# Sheet1.net
KiCad netlist of a schematic drawn in Altium Designer
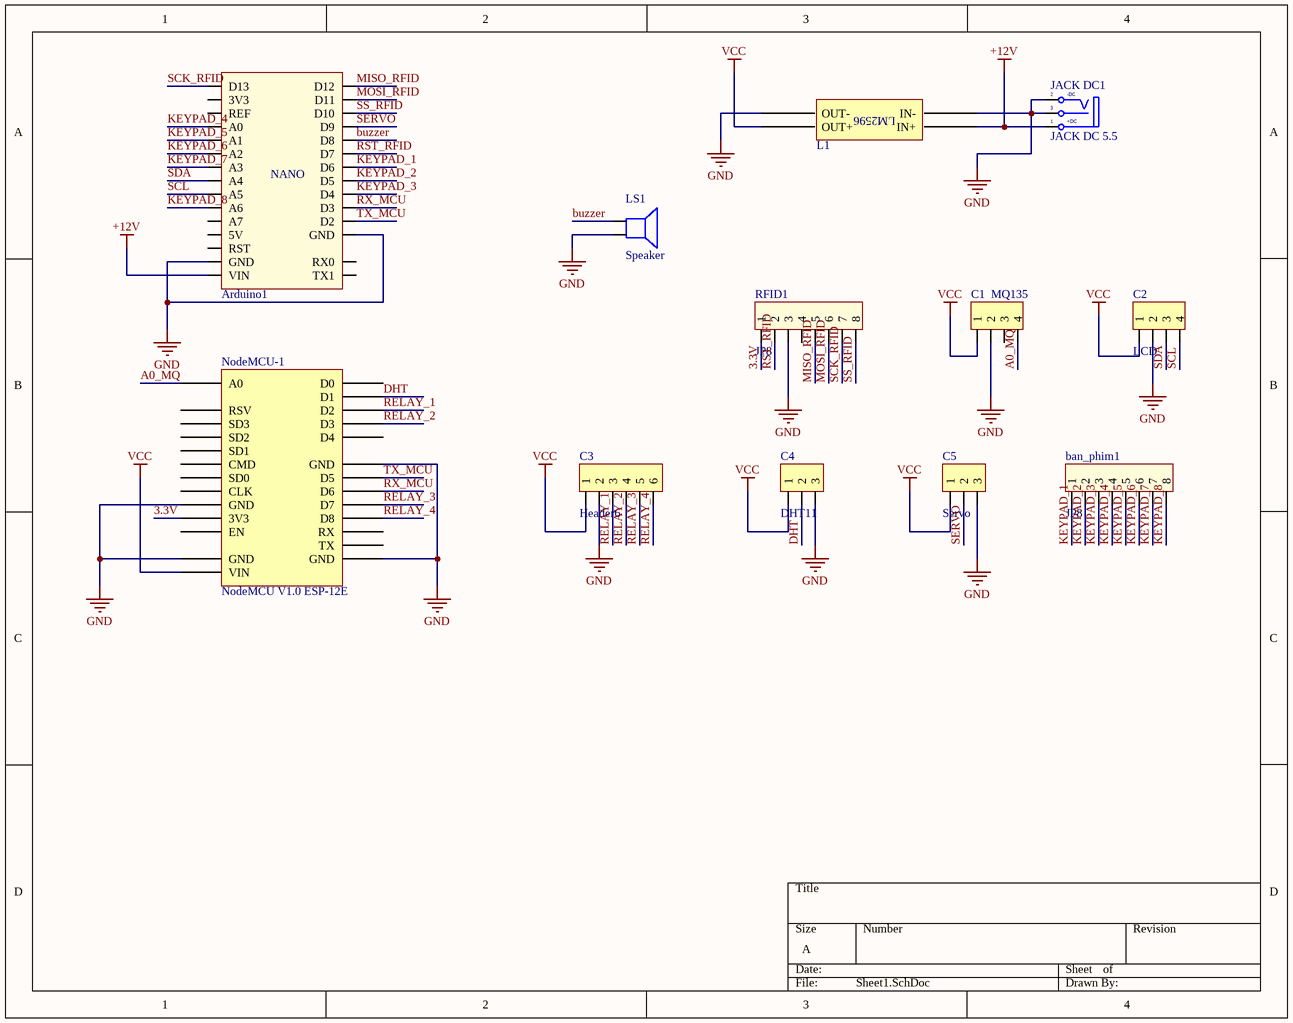
[diagram p0: Sheet1.SchDoc]

(export (version "E")
  (design (tool "Eeschema 10.0.6"))
  (components
    (comp (ref "Arduino1")
      (value "Arduino Nano")
      (footprint "Arduino Nano")
      (description "Arduino NANO")
      (libsource (lib "LIBRARY") (part "Arduino Nano"))
    )
    (comp (ref "ban_phim1")
      (value "JP8")
      (footprint "Header8")
      (description "Connector 8")
      (libsource (lib "LIBRARY") (part "Header8"))
    )
    (comp (ref "C1")
      (value "MQ135")
      (footprint "HDR4")
      (description "Header IDC, 4 x 1 Pin Vertical 2.54mm Pitch (Non-Boxed, Male)")
      (fields
        (field (name "MANUFACTURER") "Würth Elektronik eiSos GmbH")
        (field (name "PARTNO") "613002143121")
        (field (name "CREATED BY") "Karrer Zheng")
      )
      (libsource (lib "LIBRARY") (part "Header4"))
    )
    (comp (ref "C2")
      (value "LCD")
      (footprint "HDR4")
      (description "Header IDC, 4 x 1 Pin Vertical 2.54mm Pitch (Non-Boxed, Male)")
      (fields
        (field (name "MANUFACTURER") "Würth Elektronik eiSos GmbH")
        (field (name "PARTNO") "613002143121")
        (field (name "CREATED BY") "Karrer Zheng")
      )
      (libsource (lib "LIBRARY") (part "Header4"))
    )
    (comp (ref "C3")
      (value "Header6")
      (footprint "HDR6")
      (description "Header IDC, 6 x 1 Pin Vertical 2.54mm Pitch (Non-Boxed, Male)")
      (fields
        (field (name "MANUFACTURER") "Würth Elektronik eiSos GmbH")
        (field (name "PARTNO") "613002143121")
        (field (name "CREATED BY") "Karrer Zheng")
      )
      (libsource (lib "LIBRARY") (part "Header6"))
    )
    (comp (ref "C4")
      (value "DHT11")
      (footprint "HDR3")
      (description "Header IDC, 3 x 1 Pin Vertical 2.54mm Pitch (Non-Boxed, Male)")
      (fields
        (field (name "MANUFACTURER") "Würth Elektronik eiSos GmbH")
        (field (name "PARTNO") "613002143121")
        (field (name "CREATED BY") "Karrer Zheng")
      )
      (libsource (lib "LIBRARY") (part "Header3"))
    )
    (comp (ref "C5")
      (value "Servo")
      (footprint "HDR3")
      (description "Header IDC, 3 x 1 Pin Vertical 2.54mm Pitch (Non-Boxed, Male)")
      (fields
        (field (name "MANUFACTURER") "Würth Elektronik eiSos GmbH")
        (field (name "PARTNO") "613002143121")
        (field (name "CREATED BY") "Karrer Zheng")
      )
      (libsource (lib "LIBRARY") (part "Header3"))
    )
    (comp (ref "JACK DC1")
      (value "JACK DC 5.5")
      (footprint "JACK DC 5.5")
      (libsource (lib "LinhKienMCU.com") (part "JACK DC 5.5"))
    )
    (comp (ref "L1")
      (value "BUCK_LM2596")
      (footprint "BUCK_LM2596")
      (libsource (lib "BUCK_LM2596_Sch") (part "BUCK_LM2596"))
    )
    (comp (ref "LS1")
      (value "Speaker")
      (footprint "SPEAKER")
      (description "Loudspeaker")
      (fields (field (name "PUBLISHER") "Altium Limited"))
      (libsource (lib "LIBRARY") (part "Speaker"))
    )
    (comp (ref "NodeMCU-1")
      (value "NodeMCU V1.0 ESP-12E")
      (footprint "NodeMCU V1.0 ESP-12E")
      (description "NodeMCU V1.0 ESP8266 (ESP-12E)")
      (libsource (lib "nodemcu") (part "NodeMCU V1.0 ESP-12E"))
    )
    (comp (ref "RFID1")
      (value "JP8")
      (footprint "Header8")
      (description "Connector 8")
      (libsource (lib "LIBRARY") (part "Header8"))
    )
  )
  (nets
    (net (code "1") (name "+12V") (class "Default")
      (node (ref "Arduino1") (pin "VIN") (pinfunction "VIN_VIN") (pintype "passive"))
      (node (ref "JACK DC1") (pin "1") (pinfunction "T_1") (pintype "passive"))
      (node (ref "L1") (pin "1") (pinfunction "IN+_1") (pintype "passive"))
    )
    (net (code "2") (name "/3.3V") (class "Default")
      (node (ref "NodeMCU-1") (pin "3V3") (pinfunction "3V3_3V3") (pintype "passive"))
      (node (ref "RFID1") (pin "1") (pinfunction "1_1") (pintype "passive"))
    )
    (net (code "3") (name "/A0_MQ") (class "Default")
      (node (ref "C1") (pin "4") (pinfunction "4_4") (pintype "passive"))
      (node (ref "NodeMCU-1") (pin "A0") (pinfunction "A0_A0") (pintype "passive"))
    )
    (net (code "4") (name "/DHT") (class "Default")
      (node (ref "C4") (pin "2") (pinfunction "2_2") (pintype "passive"))
      (node (ref "NodeMCU-1") (pin "D1") (pinfunction "D1_D1") (pintype "passive"))
    )
    (net (code "5") (name "/KEYPAD_1") (class "Default")
      (node (ref "Arduino1") (pin "D6") (pinfunction "D6_D6") (pintype "passive"))
      (node (ref "ban_phim1") (pin "1") (pinfunction "1_1") (pintype "passive"))
    )
    (net (code "6") (name "/KEYPAD_2") (class "Default")
      (node (ref "Arduino1") (pin "D5") (pinfunction "D5_D5") (pintype "passive"))
      (node (ref "ban_phim1") (pin "2") (pinfunction "2_2") (pintype "passive"))
    )
    (net (code "7") (name "/KEYPAD_3") (class "Default")
      (node (ref "Arduino1") (pin "D4") (pinfunction "D4_D4") (pintype "passive"))
      (node (ref "ban_phim1") (pin "3") (pinfunction "3_3") (pintype "passive"))
    )
    (net (code "8") (name "/KEYPAD_4") (class "Default")
      (node (ref "Arduino1") (pin "A0") (pinfunction "A0_A0") (pintype "passive"))
      (node (ref "ban_phim1") (pin "4") (pinfunction "4_4") (pintype "passive"))
    )
    (net (code "9") (name "/KEYPAD_5") (class "Default")
      (node (ref "Arduino1") (pin "A1") (pinfunction "A1_A1") (pintype "passive"))
      (node (ref "ban_phim1") (pin "5") (pinfunction "5_5") (pintype "passive"))
    )
    (net (code "10") (name "/KEYPAD_6") (class "Default")
      (node (ref "Arduino1") (pin "A2") (pinfunction "A2_A2") (pintype "passive"))
      (node (ref "ban_phim1") (pin "6") (pinfunction "6_6") (pintype "passive"))
    )
    (net (code "11") (name "/KEYPAD_7") (class "Default")
      (node (ref "Arduino1") (pin "A3") (pinfunction "A3_A3") (pintype "passive"))
      (node (ref "ban_phim1") (pin "7") (pinfunction "7_7") (pintype "passive"))
    )
    (net (code "12") (name "/KEYPAD_8") (class "Default")
      (node (ref "Arduino1") (pin "A6") (pinfunction "A6_A6") (pintype "passive"))
      (node (ref "ban_phim1") (pin "8") (pinfunction "8_8") (pintype "passive"))
    )
    (net (code "13") (name "/MISO_RFID") (class "Default")
      (node (ref "Arduino1") (pin "D12") (pinfunction "D12_D12") (pintype "passive"))
      (node (ref "RFID1") (pin "5") (pinfunction "5_5") (pintype "passive"))
    )
    (net (code "14") (name "/MOSI_RFID") (class "Default")
      (node (ref "Arduino1") (pin "D11") (pinfunction "D11_D11") (pintype "passive"))
      (node (ref "RFID1") (pin "6") (pinfunction "6_6") (pintype "passive"))
    )
    (net (code "15") (name "/RELAY_1") (class "Default")
      (node (ref "C3") (pin "3") (pinfunction "3_3") (pintype "passive"))
      (node (ref "NodeMCU-1") (pin "D2") (pinfunction "D2_D2") (pintype "passive"))
    )
    (net (code "16") (name "/RELAY_2") (class "Default")
      (node (ref "C3") (pin "4") (pinfunction "4_4") (pintype "passive"))
      (node (ref "NodeMCU-1") (pin "D3") (pinfunction "D3_D3") (pintype "passive"))
    )
    (net (code "17") (name "/RELAY_3") (class "Default")
      (node (ref "C3") (pin "5") (pinfunction "5_5") (pintype "passive"))
      (node (ref "NodeMCU-1") (pin "D7") (pinfunction "D7_D7") (pintype "passive"))
    )
    (net (code "18") (name "/RELAY_4") (class "Default")
      (node (ref "C3") (pin "6") (pinfunction "6_6") (pintype "passive"))
      (node (ref "NodeMCU-1") (pin "D8") (pinfunction "D8_D8") (pintype "passive"))
    )
    (net (code "19") (name "/RST_RFID") (class "Default")
      (node (ref "Arduino1") (pin "D7") (pinfunction "D7_D7") (pintype "passive"))
      (node (ref "RFID1") (pin "2") (pinfunction "2_2") (pintype "passive"))
    )
    (net (code "20") (name "/RX_MCU") (class "Default")
      (node (ref "Arduino1") (pin "D3") (pinfunction "D3_D3") (pintype "passive"))
      (node (ref "NodeMCU-1") (pin "D6") (pinfunction "D6_D6") (pintype "passive"))
    )
    (net (code "21") (name "/SCK_RFID") (class "Default")
      (node (ref "Arduino1") (pin "D13") (pinfunction "D13_D13") (pintype "passive"))
      (node (ref "RFID1") (pin "7") (pinfunction "7_7") (pintype "passive"))
    )
    (net (code "22") (name "/SCL") (class "Default")
      (node (ref "Arduino1") (pin "A5") (pinfunction "A5_A5") (pintype "passive"))
      (node (ref "C2") (pin "4") (pinfunction "4_4") (pintype "passive"))
    )
    (net (code "23") (name "/SDA") (class "Default")
      (node (ref "Arduino1") (pin "A4") (pinfunction "A4_A4") (pintype "passive"))
      (node (ref "C2") (pin "3") (pinfunction "3_3") (pintype "passive"))
    )
    (net (code "24") (name "/SERVO") (class "Default")
      (node (ref "Arduino1") (pin "D9") (pinfunction "D9_D9") (pintype "passive"))
      (node (ref "C5") (pin "2") (pinfunction "2_2") (pintype "passive"))
    )
    (net (code "25") (name "/SS_RFID") (class "Default")
      (node (ref "Arduino1") (pin "D10") (pinfunction "D10_D10") (pintype "passive"))
      (node (ref "RFID1") (pin "8") (pinfunction "8_8") (pintype "passive"))
    )
    (net (code "26") (name "/TX_MCU") (class "Default")
      (node (ref "Arduino1") (pin "D2") (pinfunction "D2_D2") (pintype "passive"))
      (node (ref "NodeMCU-1") (pin "D5") (pinfunction "D5_D5") (pintype "passive"))
    )
    (net (code "27") (name "/buzzer") (class "Default")
      (node (ref "Arduino1") (pin "D8") (pinfunction "D8_D8") (pintype "passive"))
      (node (ref "LS1") (pin "1") (pinfunction "1_1") (pintype "passive"))
    )
    (net (code "28") (name "GND") (class "Default")
      (node (ref "Arduino1") (pin "GND") (pinfunction "GND_GND") (pintype "passive"))
      (node (ref "C1") (pin "2") (pinfunction "2_2") (pintype "passive"))
      (node (ref "C2") (pin "2") (pinfunction "2_2") (pintype "passive"))
      (node (ref "C3") (pin "2") (pinfunction "2_2") (pintype "passive"))
      (node (ref "C4") (pin "3") (pinfunction "3_3") (pintype "passive"))
      (node (ref "C5") (pin "3") (pinfunction "3_3") (pintype "passive"))
      (node (ref "JACK DC1") (pin "2") (pinfunction "TN_2") (pintype "passive"))
      (node (ref "JACK DC1") (pin "3") (pinfunction "S_3") (pintype "power_in"))
      (node (ref "L1") (pin "2") (pinfunction "IN-_2") (pintype "passive"))
      (node (ref "L1") (pin "3") (pinfunction "OUT-_3") (pintype "passive"))
      (node (ref "LS1") (pin "2") (pinfunction "2_2") (pintype "passive"))
      (node (ref "NodeMCU-1") (pin "GND") (pinfunction "GND_GND") (pintype "passive"))
      (node (ref "RFID1") (pin "3") (pinfunction "3_3") (pintype "passive"))
    )
    (net (code "29") (name "VCC") (class "Default")
      (node (ref "C1") (pin "1") (pinfunction "1_1") (pintype "passive"))
      (node (ref "C2") (pin "1") (pinfunction "1_1") (pintype "passive"))
      (node (ref "C3") (pin "1") (pinfunction "1_1") (pintype "passive"))
      (node (ref "C4") (pin "1") (pinfunction "1_1") (pintype "passive"))
      (node (ref "C5") (pin "1") (pinfunction "1_1") (pintype "passive"))
      (node (ref "L1") (pin "4") (pinfunction "OUT+_4") (pintype "passive"))
      (node (ref "NodeMCU-1") (pin "VIN") (pinfunction "VIN_VIN") (pintype "passive"))
    )
    (net (code "30") (name "unconnected-(Arduino1-Pad3V3)") (class "Default")
      (node (ref "Arduino1") (pin "3V3") (pinfunction "3V3_3V3") (pintype "passive"))
    )
    (net (code "31") (name "unconnected-(Arduino1-Pad5V)") (class "Default")
      (node (ref "Arduino1") (pin "5V") (pinfunction "5V_5V") (pintype "passive"))
    )
    (net (code "32") (name "unconnected-(Arduino1-PadA7)") (class "Default")
      (node (ref "Arduino1") (pin "A7") (pinfunction "A7_A7") (pintype "passive"))
    )
    (net (code "33") (name "unconnected-(Arduino1-PadREF)") (class "Default")
      (node (ref "Arduino1") (pin "REF") (pinfunction "REF_REF") (pintype "passive"))
    )
    (net (code "34") (name "unconnected-(Arduino1-PadRST)") (class "Default")
      (node (ref "Arduino1") (pin "RST") (pinfunction "RST_RST") (pintype "passive"))
    )
    (net (code "35") (name "unconnected-(Arduino1-PadRST)_1") (class "Default")
      (node (ref "Arduino1") (pin "RST") (pinfunction "RST_RST") (pintype "passive"))
    )
    (net (code "36") (name "unconnected-(Arduino1-PadRX0)") (class "Default")
      (node (ref "Arduino1") (pin "RX0") (pinfunction "RX0_RX0") (pintype "passive"))
    )
    (net (code "37") (name "unconnected-(Arduino1-PadTX1)") (class "Default")
      (node (ref "Arduino1") (pin "TX1") (pinfunction "TX1_TX1") (pintype "passive"))
    )
    (net (code "38") (name "unconnected-(C1-Pad3)") (class "Default")
      (node (ref "C1") (pin "3") (pinfunction "3_3") (pintype "passive"))
    )
    (net (code "39") (name "unconnected-(NodeMCU-1-Pad3V3)") (class "Default")
      (node (ref "NodeMCU-1") (pin "3V3") (pinfunction "3V3_3V3") (pintype "passive"))
    )
    (net (code "40") (name "unconnected-(NodeMCU-1-Pad3V3)_1") (class "Default")
      (node (ref "NodeMCU-1") (pin "3V3") (pinfunction "3V3_3V3") (pintype "passive"))
    )
    (net (code "41") (name "unconnected-(NodeMCU-1-PadCLK)") (class "Default")
      (node (ref "NodeMCU-1") (pin "CLK") (pinfunction "CLK_CLK") (pintype "passive"))
    )
    (net (code "42") (name "unconnected-(NodeMCU-1-PadCMD)") (class "Default")
      (node (ref "NodeMCU-1") (pin "CMD") (pinfunction "CMD_CMD") (pintype "passive"))
    )
    (net (code "43") (name "unconnected-(NodeMCU-1-PadD0)") (class "Default")
      (node (ref "NodeMCU-1") (pin "D0") (pinfunction "D0_D0") (pintype "passive"))
    )
    (net (code "44") (name "unconnected-(NodeMCU-1-PadD4)") (class "Default")
      (node (ref "NodeMCU-1") (pin "D4") (pinfunction "D4_D4") (pintype "passive"))
    )
    (net (code "45") (name "unconnected-(NodeMCU-1-PadEN)") (class "Default")
      (node (ref "NodeMCU-1") (pin "EN") (pinfunction "EN_EN") (pintype "passive"))
    )
    (net (code "46") (name "unconnected-(NodeMCU-1-PadRST)") (class "Default")
      (node (ref "NodeMCU-1") (pin "RST") (pinfunction "RST_RST") (pintype "passive"))
    )
    (net (code "47") (name "unconnected-(NodeMCU-1-PadRSV)") (class "Default")
      (node (ref "NodeMCU-1") (pin "RSV") (pinfunction "RSV_RSV") (pintype "passive"))
    )
    (net (code "48") (name "unconnected-(NodeMCU-1-PadRSV)_1") (class "Default")
      (node (ref "NodeMCU-1") (pin "RSV") (pinfunction "RSV_RSV") (pintype "passive"))
    )
    (net (code "49") (name "unconnected-(NodeMCU-1-PadRX)") (class "Default")
      (node (ref "NodeMCU-1") (pin "RX") (pinfunction "RX_RX") (pintype "passive"))
    )
    (net (code "50") (name "unconnected-(NodeMCU-1-PadSD0)") (class "Default")
      (node (ref "NodeMCU-1") (pin "SD0") (pinfunction "SD0_SD0") (pintype "passive"))
    )
    (net (code "51") (name "unconnected-(NodeMCU-1-PadSD1)") (class "Default")
      (node (ref "NodeMCU-1") (pin "SD1") (pinfunction "SD1_SD1") (pintype "passive"))
    )
    (net (code "52") (name "unconnected-(NodeMCU-1-PadSD2)") (class "Default")
      (node (ref "NodeMCU-1") (pin "SD2") (pinfunction "SD2_SD2") (pintype "passive"))
    )
    (net (code "53") (name "unconnected-(NodeMCU-1-PadSD3)") (class "Default")
      (node (ref "NodeMCU-1") (pin "SD3") (pinfunction "SD3_SD3") (pintype "passive"))
    )
    (net (code "54") (name "unconnected-(NodeMCU-1-PadTX)") (class "Default")
      (node (ref "NodeMCU-1") (pin "TX") (pinfunction "TX_TX") (pintype "passive"))
    )
    (net (code "55") (name "unconnected-(RFID1-Pad4)") (class "Default")
      (node (ref "RFID1") (pin "4") (pinfunction "4_4") (pintype "passive"))
    )
  )
)
